# E-cabinet.net
KiCad netlist of a schematic drawn in EAGLE
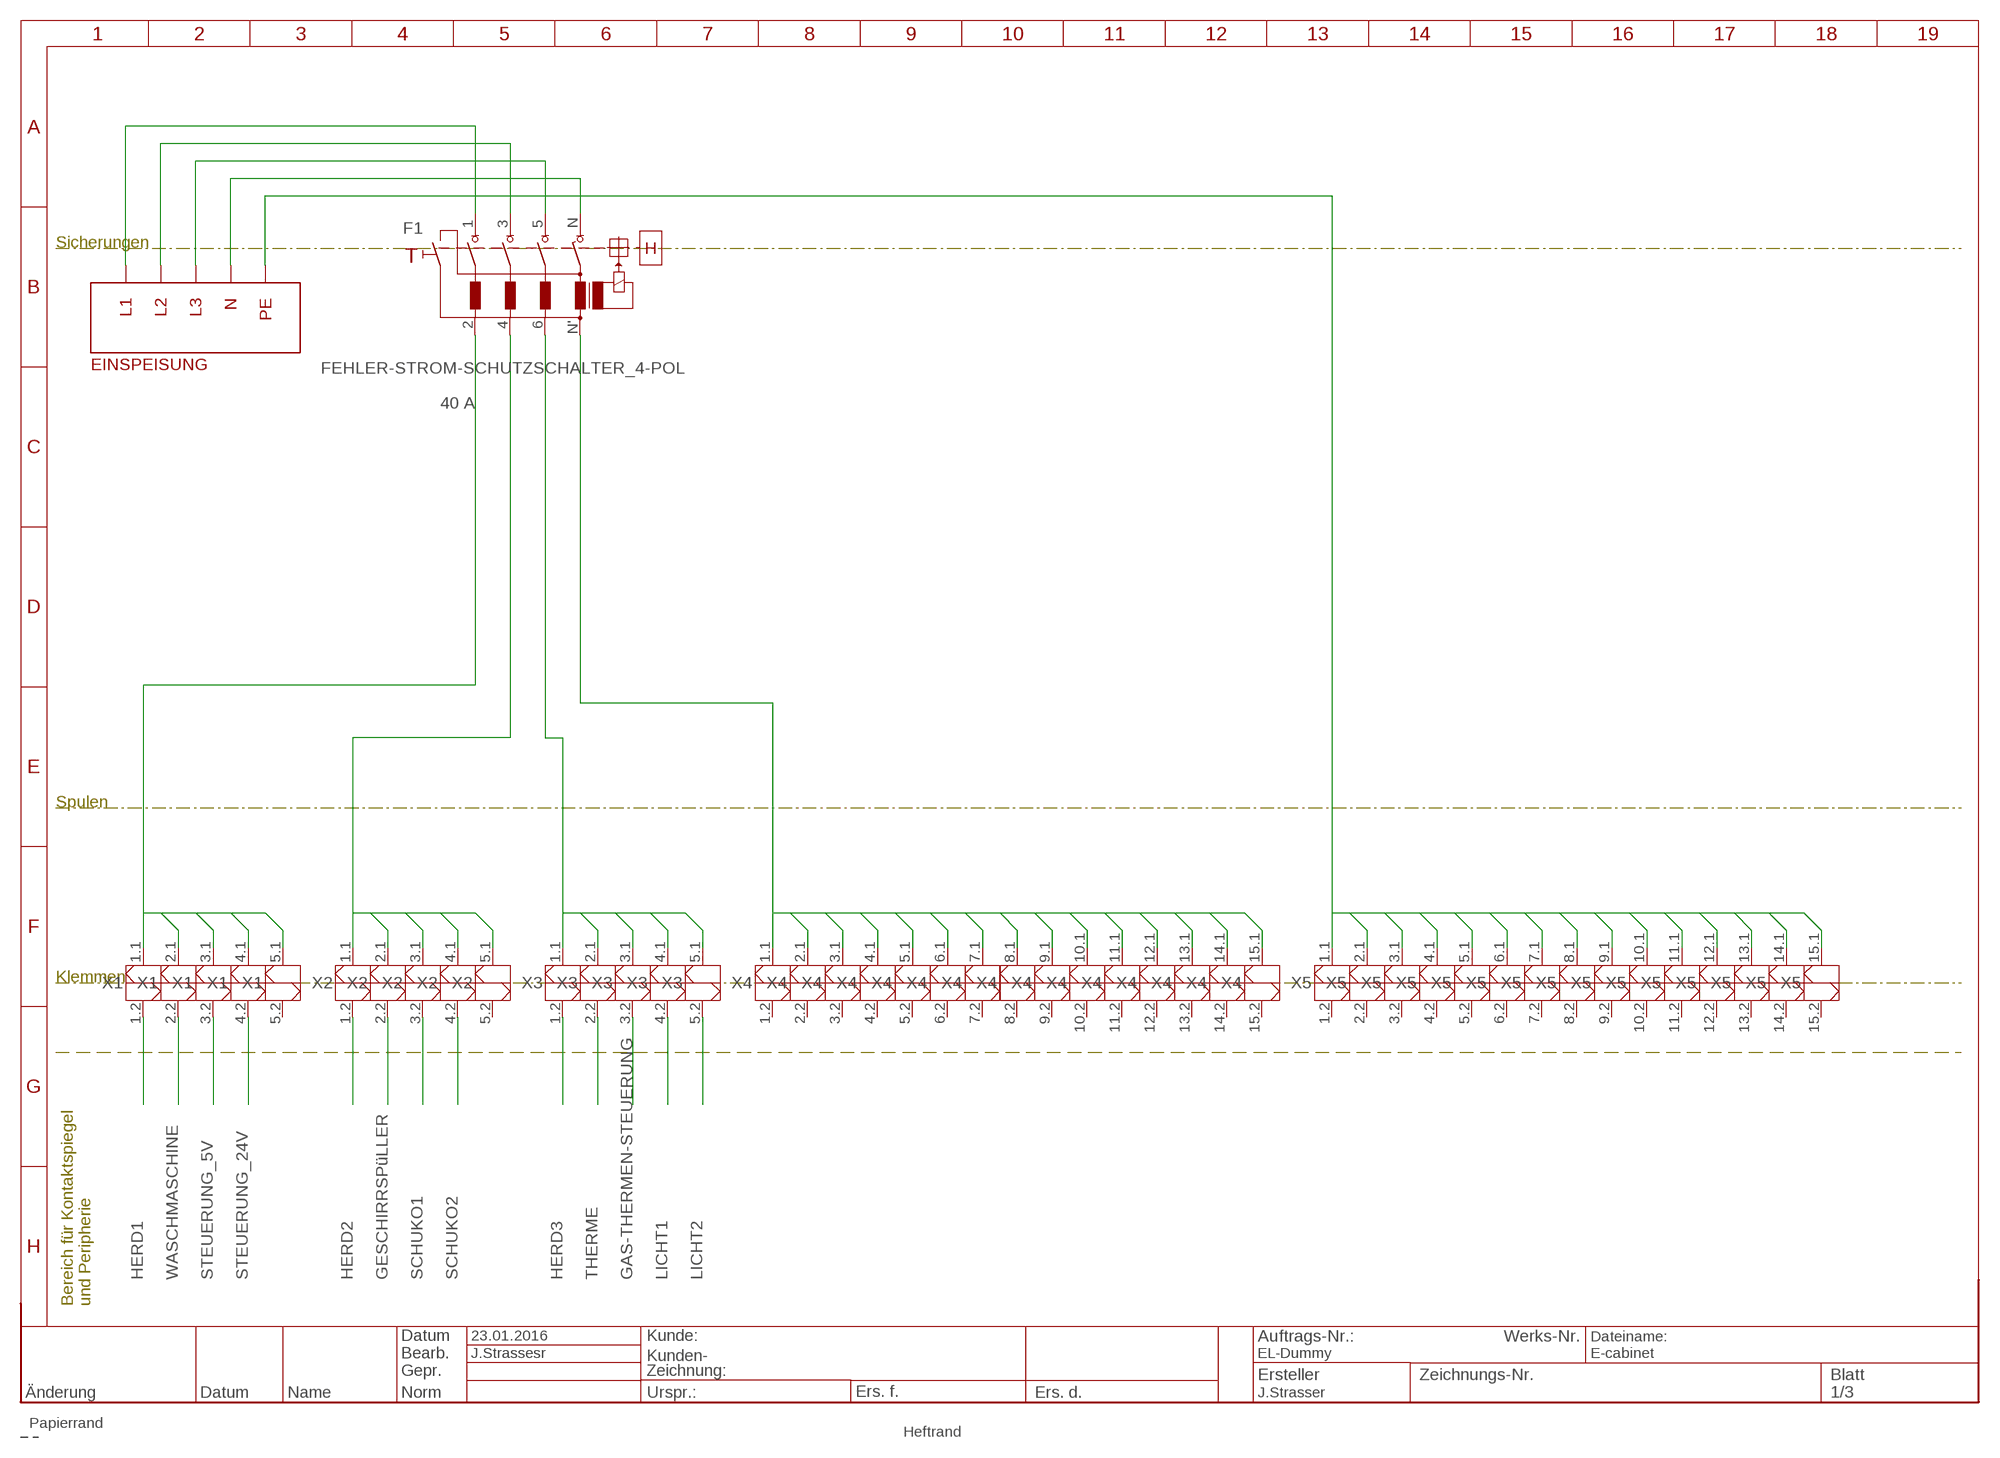
[diagram p0: schematic, sheet 1]
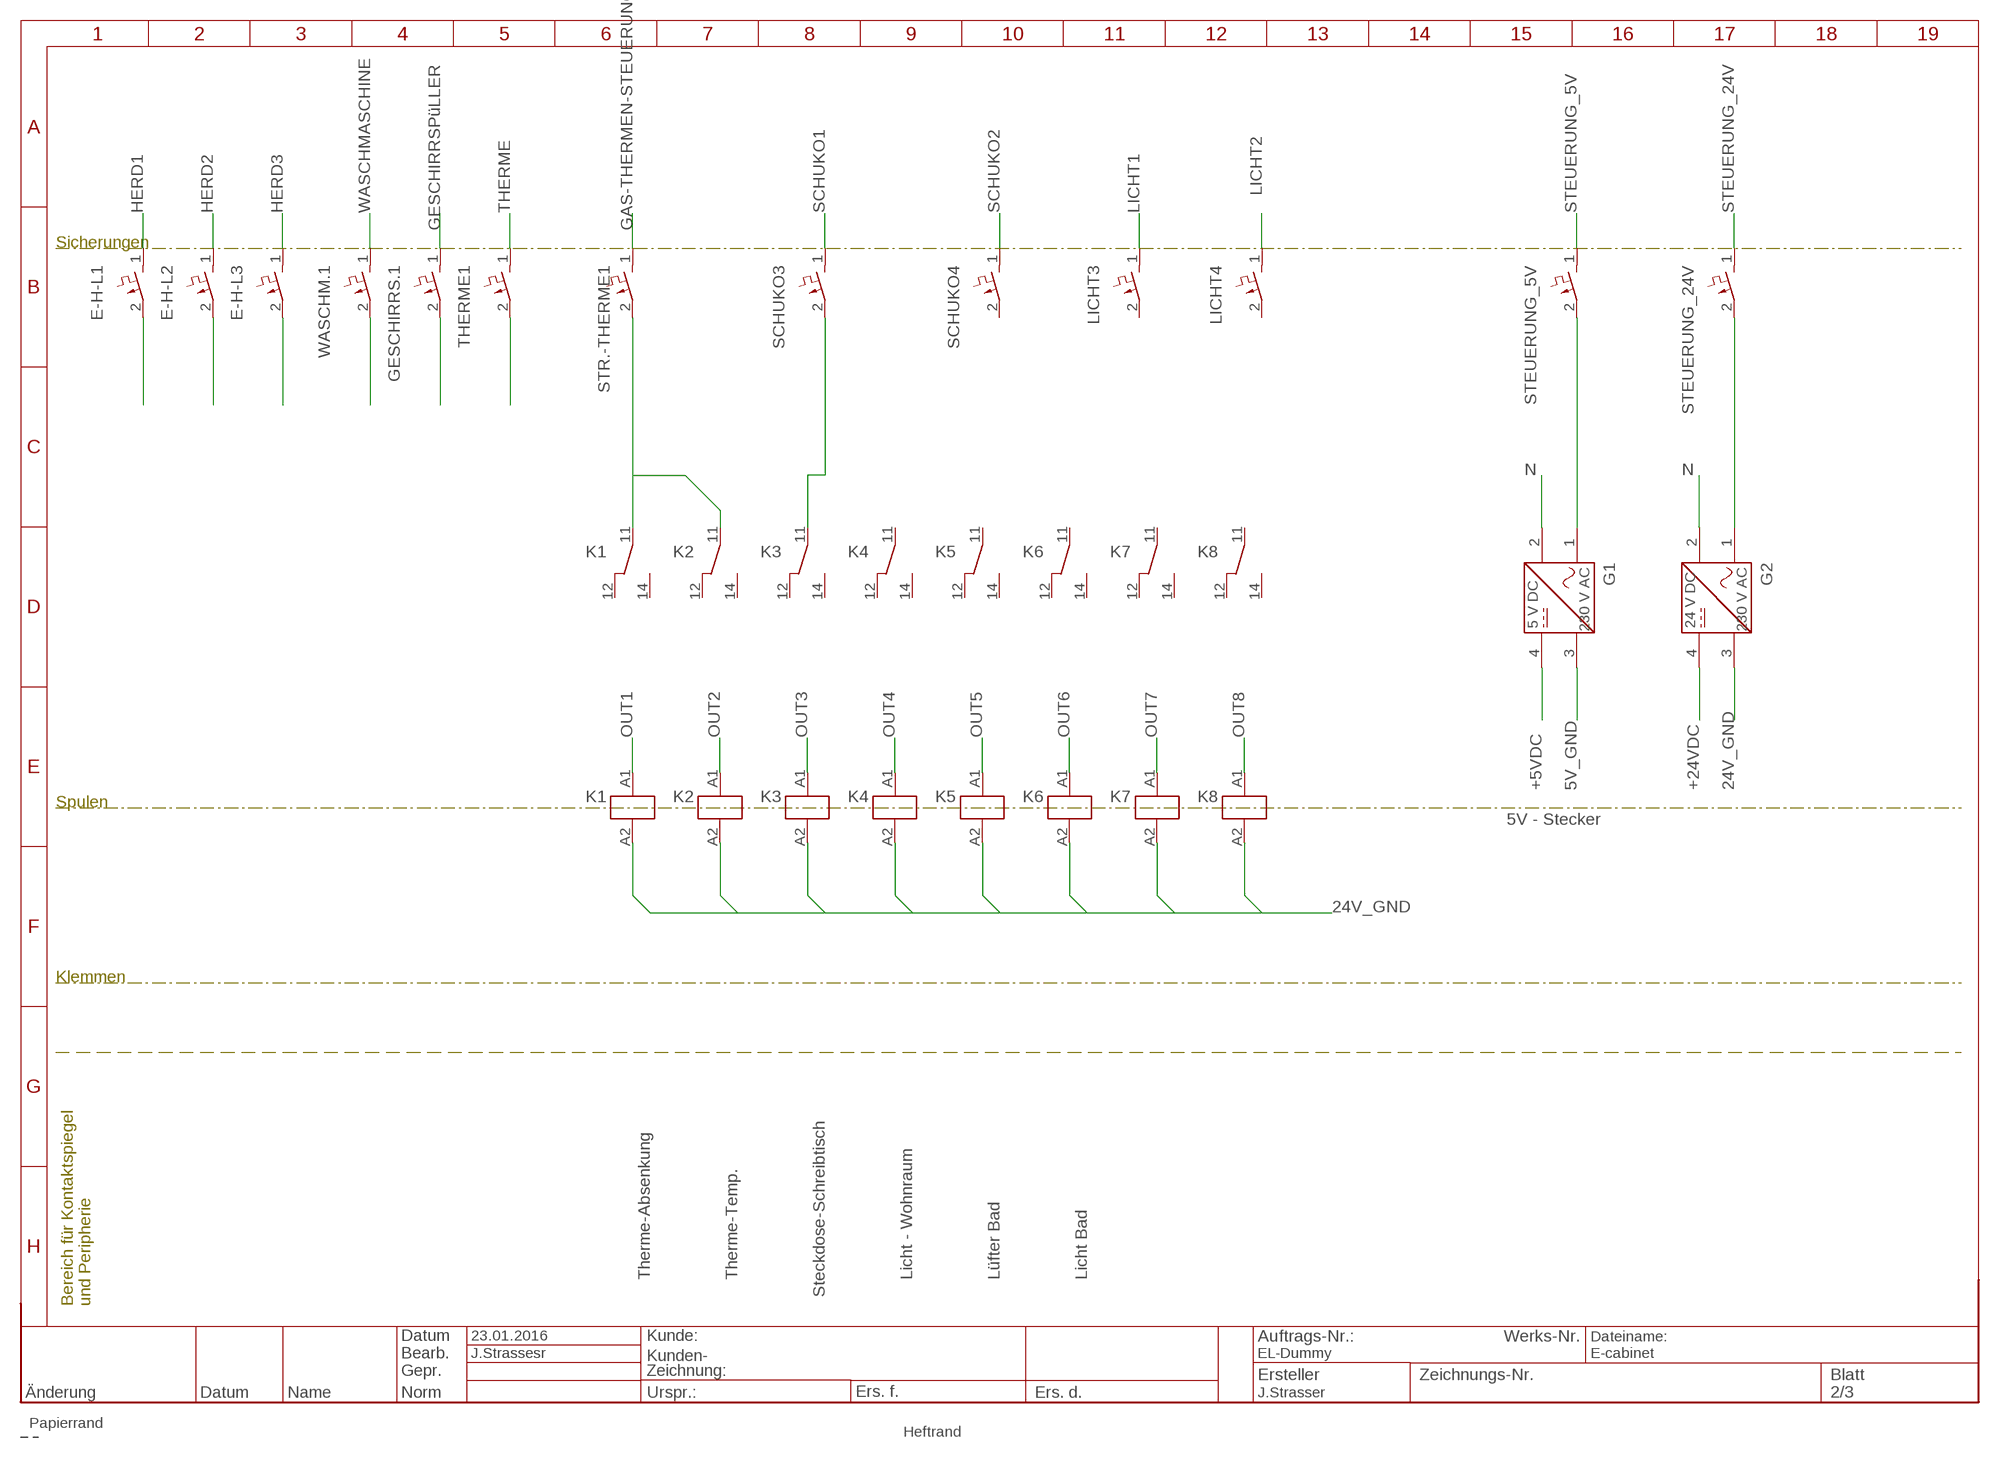
[diagram p1: schematic, sheet 2]
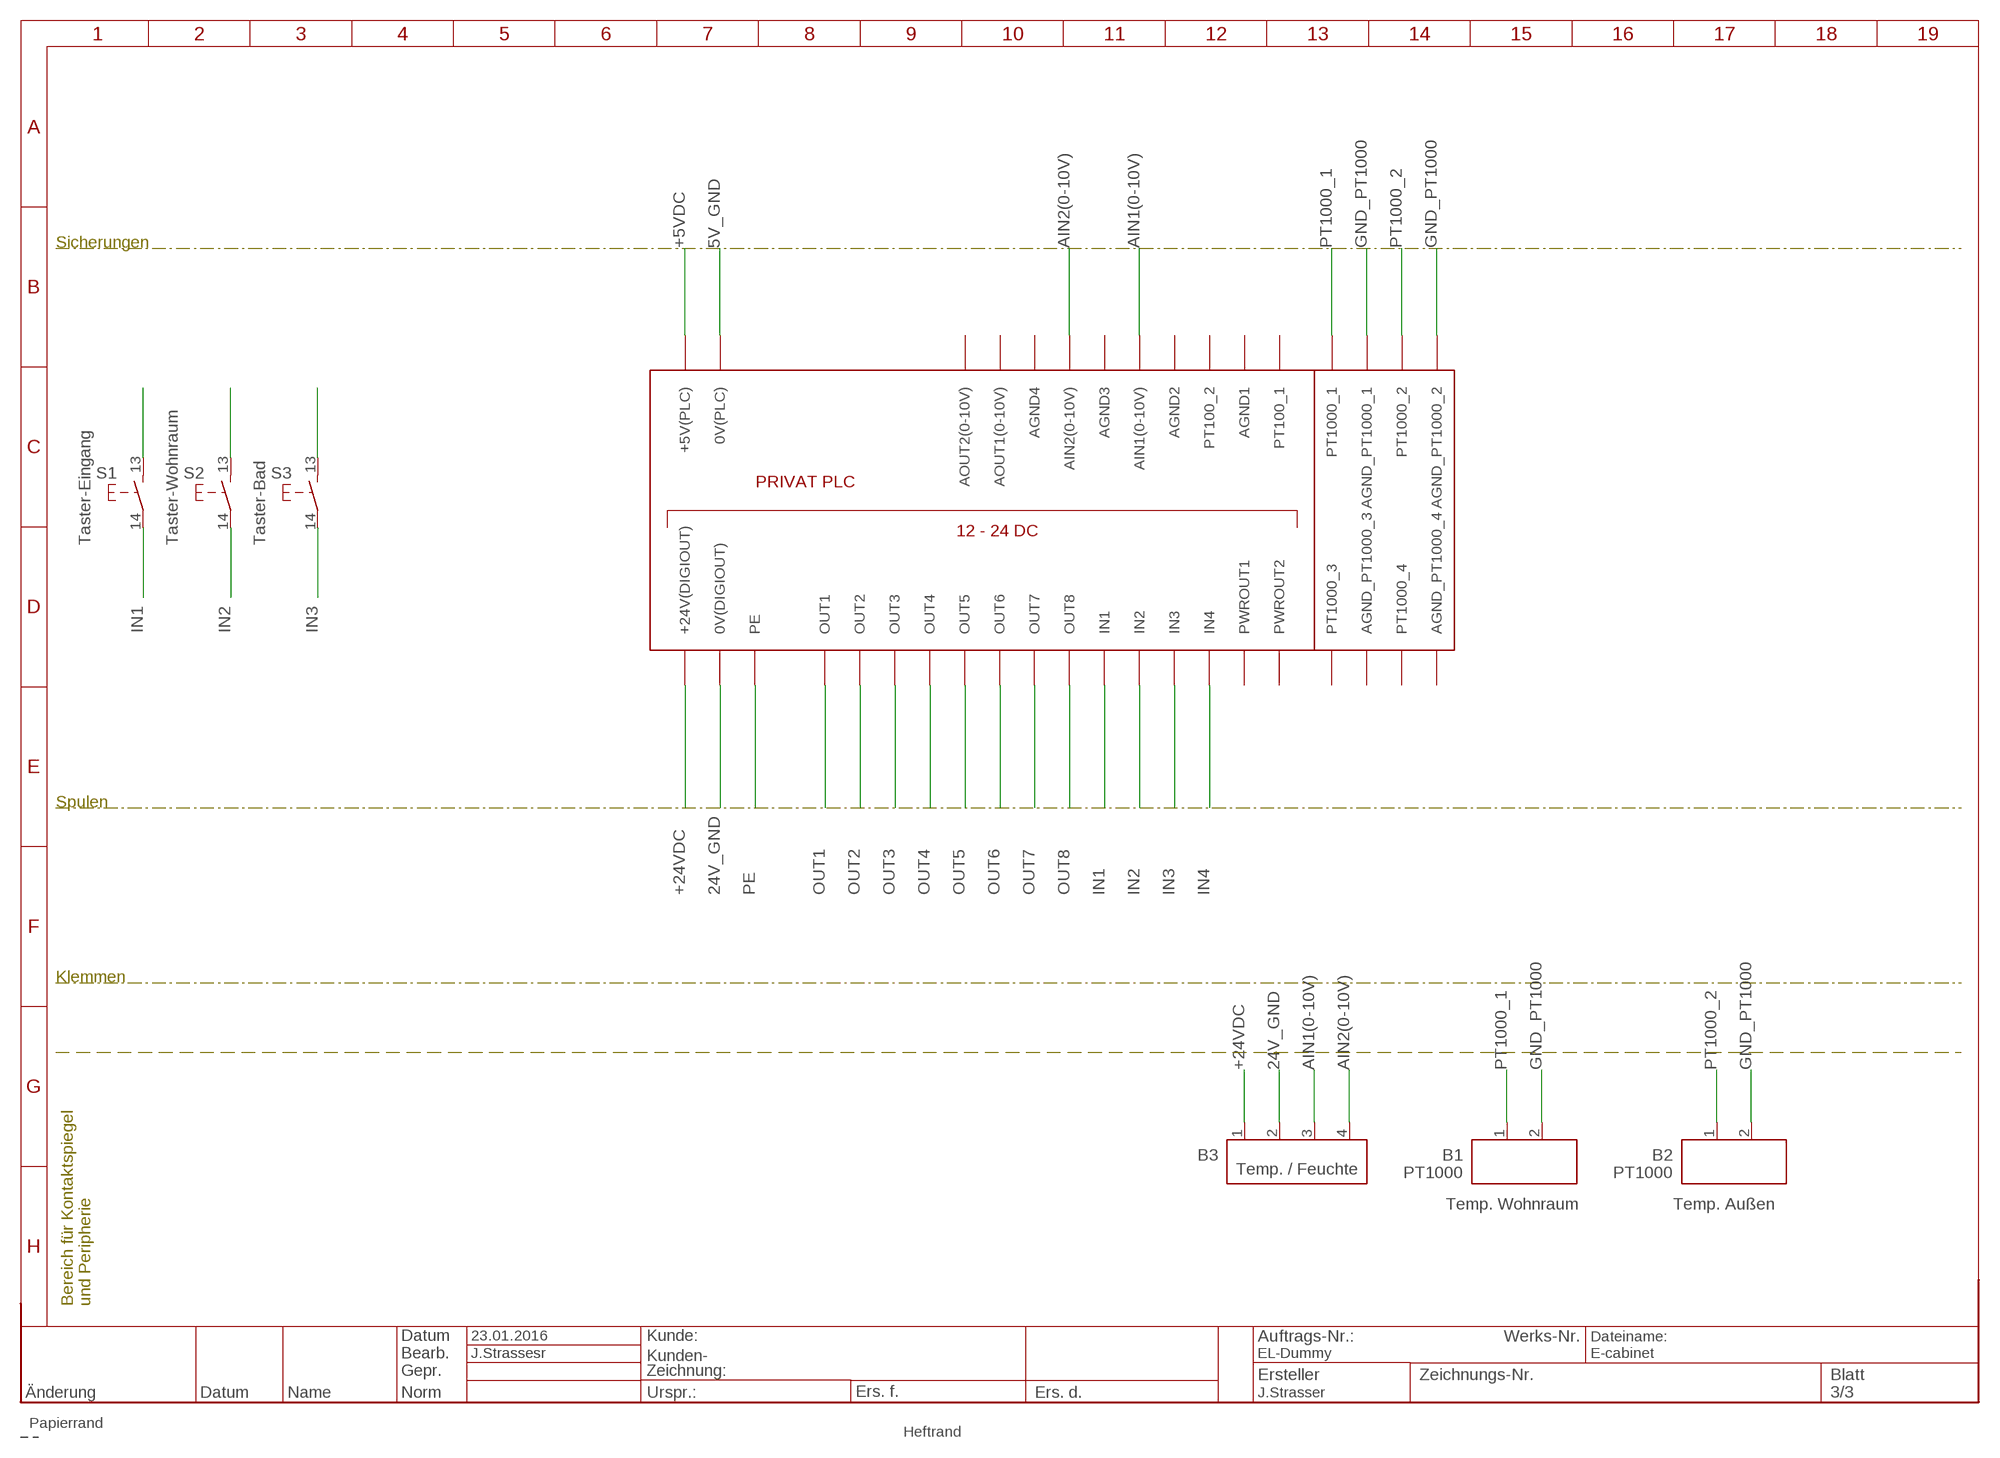
[diagram p2: schematic, sheet 3]

(export (version "E")
  (design (tool "Eeschema 10.0.6"))
  (components
    (comp (ref "E-H-L1")
      (value "LEITUNGSSCHUTZSCHALTER")
      (footprint "eagle-import:LEITUNGSSCHUTZSCHALTER")
      (libsource (lib "eagle-import") (part "LEITUNGSSCHUTZSCHALTER"))
    )
    (comp (ref "E-H-L2")
      (value "LEITUNGSSCHUTZSCHALTER")
      (footprint "eagle-import:LEITUNGSSCHUTZSCHALTER")
      (libsource (lib "eagle-import") (part "LEITUNGSSCHUTZSCHALTER"))
    )
    (comp (ref "E-H-L3")
      (value "LEITUNGSSCHUTZSCHALTER")
      (footprint "eagle-import:LEITUNGSSCHUTZSCHALTER")
      (libsource (lib "eagle-import") (part "LEITUNGSSCHUTZSCHALTER"))
    )
    (comp (ref "G1")
      (value "NETZTEIL_GLEICHSPANNUNG")
      (footprint "eagle-import:NETZTEIL_GLEICHSPANNUNG")
      (fields (field (name "AUSGANGSSPANNUNG") "5 V DC") (field (name "EINGANGSSPANNUNG") "230 V AC"))
      (libsource (lib "eagle-import") (part "NETZTEIL_GLEICHSPANNUNG"))
    )
    (comp (ref "G2")
      (value "NETZTEIL_GLEICHSPANNUNG")
      (footprint "eagle-import:NETZTEIL_GLEICHSPANNUNG")
      (fields (field (name "AUSGANGSSPANNUNG") "24 V DC") (field (name "EINGANGSSPANNUNG") "230 V AC"))
      (libsource (lib "eagle-import") (part "NETZTEIL_GLEICHSPANNUNG"))
    )
    (comp (ref "GESCHIRRS.1")
      (value "LEITUNGSSCHUTZSCHALTER")
      (footprint "eagle-import:LEITUNGSSCHUTZSCHALTER")
      (libsource (lib "eagle-import") (part "LEITUNGSSCHUTZSCHALTER"))
    )
    (comp (ref "K1")
      (value "HILFSSCHUETZ_11-12-14")
      (footprint "eagle-import:HILFSSCHUETZ_11-12-14")
      (libsource (lib "eagle-import") (part "HILFSSCHUETZ_11-12-14"))
    )
    (comp (ref "K2")
      (value "HILFSSCHUETZ_11-12-14")
      (footprint "eagle-import:HILFSSCHUETZ_11-12-14")
      (libsource (lib "eagle-import") (part "HILFSSCHUETZ_11-12-14"))
    )
    (comp (ref "K3")
      (value "HILFSSCHUETZ_11-12-14")
      (footprint "eagle-import:HILFSSCHUETZ_11-12-14")
      (libsource (lib "eagle-import") (part "HILFSSCHUETZ_11-12-14"))
    )
    (comp (ref "K4")
      (value "HILFSSCHUETZ_11-12-14")
      (footprint "eagle-import:HILFSSCHUETZ_11-12-14")
      (libsource (lib "eagle-import") (part "HILFSSCHUETZ_11-12-14"))
    )
    (comp (ref "K5")
      (value "HILFSSCHUETZ_11-12-14")
      (footprint "eagle-import:HILFSSCHUETZ_11-12-14")
      (libsource (lib "eagle-import") (part "HILFSSCHUETZ_11-12-14"))
    )
    (comp (ref "K6")
      (value "HILFSSCHUETZ_11-12-14")
      (footprint "eagle-import:HILFSSCHUETZ_11-12-14")
      (libsource (lib "eagle-import") (part "HILFSSCHUETZ_11-12-14"))
    )
    (comp (ref "K7")
      (value "HILFSSCHUETZ_11-12-14")
      (footprint "eagle-import:HILFSSCHUETZ_11-12-14")
      (libsource (lib "eagle-import") (part "HILFSSCHUETZ_11-12-14"))
    )
    (comp (ref "K8")
      (value "HILFSSCHUETZ_11-12-14")
      (footprint "eagle-import:HILFSSCHUETZ_11-12-14")
      (libsource (lib "eagle-import") (part "HILFSSCHUETZ_11-12-14"))
    )
    (comp (ref "LICHT3")
      (value "LEITUNGSSCHUTZSCHALTER")
      (footprint "eagle-import:LEITUNGSSCHUTZSCHALTER")
      (libsource (lib "eagle-import") (part "LEITUNGSSCHUTZSCHALTER"))
    )
    (comp (ref "LICHT4")
      (value "LEITUNGSSCHUTZSCHALTER")
      (footprint "eagle-import:LEITUNGSSCHUTZSCHALTER")
      (libsource (lib "eagle-import") (part "LEITUNGSSCHUTZSCHALTER"))
    )
    (comp (ref "SCHUKO3")
      (value "LEITUNGSSCHUTZSCHALTER")
      (footprint "eagle-import:LEITUNGSSCHUTZSCHALTER")
      (libsource (lib "eagle-import") (part "LEITUNGSSCHUTZSCHALTER"))
    )
    (comp (ref "SCHUKO4")
      (value "LEITUNGSSCHUTZSCHALTER")
      (footprint "eagle-import:LEITUNGSSCHUTZSCHALTER")
      (libsource (lib "eagle-import") (part "LEITUNGSSCHUTZSCHALTER"))
    )
    (comp (ref "STEUERUNG_5V")
      (value "LEITUNGSSCHUTZSCHALTER")
      (footprint "eagle-import:LEITUNGSSCHUTZSCHALTER")
      (libsource (lib "eagle-import") (part "LEITUNGSSCHUTZSCHALTER"))
    )
    (comp (ref "STEUERUNG_24V")
      (value "LEITUNGSSCHUTZSCHALTER")
      (footprint "eagle-import:LEITUNGSSCHUTZSCHALTER")
      (libsource (lib "eagle-import") (part "LEITUNGSSCHUTZSCHALTER"))
    )
    (comp (ref "STR.-THERME1")
      (value "LEITUNGSSCHUTZSCHALTER")
      (footprint "eagle-import:LEITUNGSSCHUTZSCHALTER")
      (libsource (lib "eagle-import") (part "LEITUNGSSCHUTZSCHALTER"))
    )
    (comp (ref "THERME1")
      (value "LEITUNGSSCHUTZSCHALTER")
      (footprint "eagle-import:LEITUNGSSCHUTZSCHALTER")
      (libsource (lib "eagle-import") (part "LEITUNGSSCHUTZSCHALTER"))
    )
    (comp (ref "WASCHM.1")
      (value "LEITUNGSSCHUTZSCHALTER")
      (footprint "eagle-import:LEITUNGSSCHUTZSCHALTER")
      (libsource (lib "eagle-import") (part "LEITUNGSSCHUTZSCHALTER"))
    )
    (comp (ref "B1")
      (value "MESSFUEHLER_2")
      (footprint "eagle-import:MESSFUEHLER_2")
      (fields (field (name "FUNKTION") "Temp. Wohnraum") (field (name "TYPE") "PT1000"))
      (libsource (lib "eagle-import") (part "MESSFUEHLER_2"))
    )
    (comp (ref "B2")
      (value "MESSFUEHLER_2")
      (footprint "eagle-import:MESSFUEHLER_2")
      (fields (field (name "FUNKTION") "Temp. Außen") (field (name "TYPE") "PT1000"))
      (libsource (lib "eagle-import") (part "MESSFUEHLER_2"))
    )
    (comp (ref "B3")
      (value "MESSFUEHLER_4")
      (footprint "eagle-import:MESSFUEHLER_4")
      (fields (field (name "FUNKTION") "Temp. / Feuchte"))
      (libsource (lib "eagle-import") (part "MESSFUEHLER_4"))
    )
    (comp (ref "S1")
      (value "TASTER_SCHLIESSER")
      (footprint "eagle-import:EINTASTER")
      (libsource (lib "eagle-import") (part "TASTER_SCHLIESSER"))
    )
    (comp (ref "S2")
      (value "TASTER_SCHLIESSER")
      (footprint "eagle-import:EINTASTER")
      (libsource (lib "eagle-import") (part "TASTER_SCHLIESSER"))
    )
    (comp (ref "S3")
      (value "TASTER_SCHLIESSER")
      (footprint "eagle-import:EINTASTER")
      (libsource (lib "eagle-import") (part "TASTER_SCHLIESSER"))
    )
    (comp (ref "U$1")
      (value "PRIVATEPLC")
      (footprint "eagle-import:PRIVATEPLC")
      (libsource (lib "eagle-import") (part "PRIVATEPLC"))
    )
    (comp (ref "F1")
      (value "FEHLER-STROM-SCHUTZSCHALTER_4-POL")
      (footprint "eagle-import:FEHLER-STROM-SCHUTZSCHALTER_4-POL")
      (fields (field (name "FUNKTION") "40 A"))
      (libsource (lib "eagle-import") (part "FEHLER-STROM-SCHUTZSCHALTER_4-POL"))
    )
    (comp (ref "X1")
      (value "KLEMME-2_5-BRUECKE")
      (footprint "eagle-import:KLEMME-2_5-BRUECKE")
      (libsource (lib "eagle-import") (part "KLEMME-2_5-BRUECKE"))
    )
    (comp (ref "X2")
      (value "KLEMME-2_5-BRUECKE")
      (footprint "eagle-import:KLEMME-2_5-BRUECKE")
      (libsource (lib "eagle-import") (part "KLEMME-2_5-BRUECKE"))
    )
    (comp (ref "X3")
      (value "KLEMME-2_5-BRUECKE")
      (footprint "eagle-import:KLEMME-2_5-BRUECKE")
      (libsource (lib "eagle-import") (part "KLEMME-2_5-BRUECKE"))
    )
    (comp (ref "X4")
      (value "KLEMME-2_15-BRUECKE")
      (footprint "eagle-import:KLEMME-2_15-BRUECKE")
      (libsource (lib "eagle-import") (part "KLEMME-2_15-BRUECKE"))
    )
    (comp (ref "X5")
      (value "KLEMME-2_15-BRUECKE")
      (footprint "eagle-import:KLEMME-2_15-BRUECKE")
      (libsource (lib "eagle-import") (part "KLEMME-2_15-BRUECKE"))
    )
  )
  (nets
    (net (code "1") (name "+5VDC") (class "Default")
      (node (ref "G1") (pin "4") (pinfunction "4_4") (pintype "passive"))
      (node (ref "U$1") (pin "P5V") (pinfunction "+5V(PLC)_P5V") (pintype "power_in"))
    )
    (net (code "2") (name "+24VDC") (class "Default")
      (node (ref "B3") (pin "1") (pinfunction "1_1") (pintype "passive"))
      (node (ref "G2") (pin "4") (pinfunction "4_4") (pintype "passive"))
      (node (ref "U$1") (pin "+24V") (pinfunction "+24V(DIGIOUT)_+24V") (pintype "power_in"))
    )
    (net (code "3") (name "5V_GND") (class "Default")
      (node (ref "G1") (pin "3") (pinfunction "3_3") (pintype "passive"))
      (node (ref "U$1") (pin "P0V") (pinfunction "0V(PLC)_P0V") (pintype "power_in"))
    )
    (net (code "4") (name "24V_GND") (class "Default")
      (node (ref "B3") (pin "2") (pinfunction "2_2") (pintype "passive"))
      (node (ref "G2") (pin "3") (pinfunction "3_3") (pintype "passive"))
      (node (ref "K1") (pin "A2") (pinfunction "A2_A2") (pintype "input"))
      (node (ref "K2") (pin "A2") (pinfunction "A2_A2") (pintype "input"))
      (node (ref "K3") (pin "A2") (pinfunction "A2_A2") (pintype "input"))
      (node (ref "K4") (pin "A2") (pinfunction "A2_A2") (pintype "input"))
      (node (ref "K5") (pin "A2") (pinfunction "A2_A2") (pintype "input"))
      (node (ref "K6") (pin "A2") (pinfunction "A2_A2") (pintype "input"))
      (node (ref "K7") (pin "A2") (pinfunction "A2_A2") (pintype "input"))
      (node (ref "K8") (pin "A2") (pinfunction "A2_A2") (pintype "input"))
      (node (ref "U$1") (pin "0V") (pinfunction "0V(DIGIOUT)_0V") (pintype "power_in"))
    )
    (net (code "5") (name "AIN1(0-10V)") (class "Default")
      (node (ref "B3") (pin "3") (pinfunction "3_3") (pintype "passive"))
      (node (ref "U$1") (pin "AIN1") (pinfunction "AIN1(0-10V)_AIN1") (pintype "bidirectional"))
    )
    (net (code "6") (name "AIN2(0-10V)") (class "Default")
      (node (ref "B3") (pin "4") (pinfunction "4_4") (pintype "passive"))
      (node (ref "U$1") (pin "AIN2") (pinfunction "AIN2(0-10V)_AIN2") (pintype "bidirectional"))
    )
    (net (code "7") (name "GAS-THERMEN-STEUERUNG") (class "Default")
      (node (ref "STR.-THERME1") (pin "1") (pinfunction "1_1") (pintype "passive"))
      (node (ref "X3") (pin "3.2") (pinfunction "2_3.2") (pintype "passive"))
    )
    (net (code "8") (name "GESCHIRRSPüLLER") (class "Default")
      (node (ref "GESCHIRRS.1") (pin "1") (pinfunction "1_1") (pintype "passive"))
      (node (ref "X2") (pin "2.2") (pinfunction "2_2.2") (pintype "passive"))
    )
    (net (code "9") (name "GND_PT1000") (class "Default")
      (node (ref "B1") (pin "2") (pinfunction "2_2") (pintype "passive"))
      (node (ref "B2") (pin "2") (pinfunction "2_2") (pintype "passive"))
      (node (ref "U$1") (pin "AGND_PT1000_1") (pinfunction "AGND_PT1000_1_AGND_PT1000_1") (pintype "bidirectional"))
      (node (ref "U$1") (pin "AGND_PT1000_2") (pinfunction "AGND_PT1000_2_AGND_PT1000_2") (pintype "bidirectional"))
    )
    (net (code "10") (name "HERD1") (class "Default")
      (node (ref "E-H-L1") (pin "1") (pinfunction "1_1") (pintype "passive"))
      (node (ref "X1") (pin "1.2") (pinfunction "2_1.2") (pintype "passive"))
    )
    (net (code "11") (name "HERD2") (class "Default")
      (node (ref "E-H-L2") (pin "1") (pinfunction "1_1") (pintype "passive"))
      (node (ref "X2") (pin "1.2") (pinfunction "2_1.2") (pintype "passive"))
    )
    (net (code "12") (name "HERD3") (class "Default")
      (node (ref "E-H-L3") (pin "1") (pinfunction "1_1") (pintype "passive"))
      (node (ref "X3") (pin "1.2") (pinfunction "2_1.2") (pintype "passive"))
    )
    (net (code "13") (name "IN1") (class "Default")
      (node (ref "S1") (pin "14") (pinfunction "14_14") (pintype "passive"))
      (node (ref "U$1") (pin "IN1") (pinfunction "IN1_IN1") (pintype "bidirectional"))
    )
    (net (code "14") (name "IN2") (class "Default")
      (node (ref "S2") (pin "14") (pinfunction "14_14") (pintype "passive"))
      (node (ref "U$1") (pin "IN2") (pinfunction "IN2_IN2") (pintype "bidirectional"))
    )
    (net (code "15") (name "IN3") (class "Default")
      (node (ref "S3") (pin "14") (pinfunction "14_14") (pintype "passive"))
      (node (ref "U$1") (pin "IN3") (pinfunction "IN3_IN3") (pintype "bidirectional"))
    )
    (net (code "16") (name "IN4") (class "Default")
      (node (ref "U$1") (pin "IN4") (pinfunction "IN4_IN4") (pintype "bidirectional"))
    )
    (net (code "17") (name "LICHT1") (class "Default")
      (node (ref "LICHT3") (pin "1") (pinfunction "1_1") (pintype "passive"))
      (node (ref "X3") (pin "4.2") (pinfunction "2_4.2") (pintype "passive"))
    )
    (net (code "18") (name "LICHT2") (class "Default")
      (node (ref "LICHT4") (pin "1") (pinfunction "1_1") (pintype "passive"))
      (node (ref "X3") (pin "5.2") (pinfunction "2_5.2") (pintype "passive"))
    )
    (net (code "19") (name "N") (class "Default")
      (node (ref "F1") (pin "N'") (pinfunction "N'_N'") (pintype "passive"))
      (node (ref "G1") (pin "2") (pinfunction "2_2") (pintype "passive"))
      (node (ref "G2") (pin "2") (pinfunction "2_2") (pintype "passive"))
      (node (ref "X4") (pin "1.1") (pinfunction "1_1.1") (pintype "passive"))
      (node (ref "X4") (pin "10.1") (pinfunction "1_10.1") (pintype "passive"))
      (node (ref "X4") (pin "11.1") (pinfunction "1_11.1") (pintype "passive"))
      (node (ref "X4") (pin "12.1") (pinfunction "1_12.1") (pintype "passive"))
      (node (ref "X4") (pin "13.1") (pinfunction "1_13.1") (pintype "passive"))
      (node (ref "X4") (pin "14.1") (pinfunction "1_14.1") (pintype "passive"))
      (node (ref "X4") (pin "15.1") (pinfunction "1_15.1") (pintype "passive"))
      (node (ref "X4") (pin "2.1") (pinfunction "1_2.1") (pintype "passive"))
      (node (ref "X4") (pin "3.1") (pinfunction "1_3.1") (pintype "passive"))
      (node (ref "X4") (pin "4.1") (pinfunction "1_4.1") (pintype "passive"))
      (node (ref "X4") (pin "5.1") (pinfunction "1_5.1") (pintype "passive"))
      (node (ref "X4") (pin "6.1") (pinfunction "1_6.1") (pintype "passive"))
      (node (ref "X4") (pin "7.1") (pinfunction "1_7.1") (pintype "passive"))
      (node (ref "X4") (pin "8.1") (pinfunction "1_8.1") (pintype "passive"))
      (node (ref "X4") (pin "9.1") (pinfunction "1_9.1") (pintype "passive"))
    )
    (net (code "20") (name "Net-(F1-Pad1)") (class "Default")
      (node (ref "F1") (pin "1") (pinfunction "1_1") (pintype "passive"))
    )
    (net (code "21") (name "Net-(F1-Pad3)") (class "Default")
      (node (ref "F1") (pin "3") (pinfunction "3_3") (pintype "passive"))
    )
    (net (code "22") (name "Net-(F1-Pad5)") (class "Default")
      (node (ref "F1") (pin "5") (pinfunction "5_5") (pintype "passive"))
    )
    (net (code "23") (name "Net-(F1-PadN)") (class "Default")
      (node (ref "F1") (pin "N") (pinfunction "N_N") (pintype "passive"))
    )
    (net (code "24") (name "Net-(G1-Pad1)") (class "Default")
      (node (ref "G1") (pin "1") (pinfunction "1_1") (pintype "passive"))
      (node (ref "STEUERUNG_5V") (pin "2") (pinfunction "2_2") (pintype "passive"))
    )
    (net (code "25") (name "Net-(G2-Pad1)") (class "Default")
      (node (ref "G2") (pin "1") (pinfunction "1_1") (pintype "passive"))
      (node (ref "STEUERUNG_24V") (pin "2") (pinfunction "2_2") (pintype "passive"))
    )
    (net (code "26") (name "Net-(K1B-1)") (class "Default")
      (node (ref "K1") (pin "11") (pinfunction "1_11") (pintype "passive"))
      (node (ref "K2") (pin "11") (pinfunction "1_11") (pintype "passive"))
      (node (ref "STR.-THERME1") (pin "2") (pinfunction "2_2") (pintype "passive"))
    )
    (net (code "27") (name "Net-(K3B-1)") (class "Default")
      (node (ref "K3") (pin "11") (pinfunction "1_11") (pintype "passive"))
      (node (ref "SCHUKO3") (pin "2") (pinfunction "2_2") (pintype "passive"))
    )
    (net (code "28") (name "Net-(X1A-1)") (class "Default")
      (node (ref "F1") (pin "2") (pinfunction "2_2") (pintype "passive"))
      (node (ref "X1") (pin "1.1") (pinfunction "1_1.1") (pintype "passive"))
      (node (ref "X1") (pin "2.1") (pinfunction "1_2.1") (pintype "passive"))
      (node (ref "X1") (pin "3.1") (pinfunction "1_3.1") (pintype "passive"))
      (node (ref "X1") (pin "4.1") (pinfunction "1_4.1") (pintype "passive"))
      (node (ref "X1") (pin "5.1") (pinfunction "1_5.1") (pintype "passive"))
    )
    (net (code "29") (name "Net-(X2A-1)") (class "Default")
      (node (ref "F1") (pin "4") (pinfunction "4_4") (pintype "passive"))
      (node (ref "X2") (pin "1.1") (pinfunction "1_1.1") (pintype "passive"))
      (node (ref "X2") (pin "2.1") (pinfunction "1_2.1") (pintype "passive"))
      (node (ref "X2") (pin "3.1") (pinfunction "1_3.1") (pintype "passive"))
      (node (ref "X2") (pin "4.1") (pinfunction "1_4.1") (pintype "passive"))
      (node (ref "X2") (pin "5.1") (pinfunction "1_5.1") (pintype "passive"))
    )
    (net (code "30") (name "Net-(X3A-1)") (class "Default")
      (node (ref "F1") (pin "6") (pinfunction "6_6") (pintype "passive"))
      (node (ref "X3") (pin "1.1") (pinfunction "1_1.1") (pintype "passive"))
      (node (ref "X3") (pin "2.1") (pinfunction "1_2.1") (pintype "passive"))
      (node (ref "X3") (pin "3.1") (pinfunction "1_3.1") (pintype "passive"))
      (node (ref "X3") (pin "4.1") (pinfunction "1_4.1") (pintype "passive"))
      (node (ref "X3") (pin "5.1") (pinfunction "1_5.1") (pintype "passive"))
    )
    (net (code "31") (name "Net-(X5A-1)") (class "Default")
      (node (ref "X5") (pin "1.1") (pinfunction "1_1.1") (pintype "passive"))
      (node (ref "X5") (pin "10.1") (pinfunction "1_10.1") (pintype "passive"))
      (node (ref "X5") (pin "11.1") (pinfunction "1_11.1") (pintype "passive"))
      (node (ref "X5") (pin "12.1") (pinfunction "1_12.1") (pintype "passive"))
      (node (ref "X5") (pin "13.1") (pinfunction "1_13.1") (pintype "passive"))
      (node (ref "X5") (pin "14.1") (pinfunction "1_14.1") (pintype "passive"))
      (node (ref "X5") (pin "15.1") (pinfunction "1_15.1") (pintype "passive"))
      (node (ref "X5") (pin "2.1") (pinfunction "1_2.1") (pintype "passive"))
      (node (ref "X5") (pin "3.1") (pinfunction "1_3.1") (pintype "passive"))
      (node (ref "X5") (pin "4.1") (pinfunction "1_4.1") (pintype "passive"))
      (node (ref "X5") (pin "5.1") (pinfunction "1_5.1") (pintype "passive"))
      (node (ref "X5") (pin "6.1") (pinfunction "1_6.1") (pintype "passive"))
      (node (ref "X5") (pin "7.1") (pinfunction "1_7.1") (pintype "passive"))
      (node (ref "X5") (pin "8.1") (pinfunction "1_8.1") (pintype "passive"))
      (node (ref "X5") (pin "9.1") (pinfunction "1_9.1") (pintype "passive"))
    )
    (net (code "32") (name "OUT1") (class "Default")
      (node (ref "K1") (pin "A1") (pinfunction "A1_A1") (pintype "input"))
      (node (ref "U$1") (pin "OUT1") (pinfunction "OUT1_OUT1") (pintype "bidirectional"))
    )
    (net (code "33") (name "OUT2") (class "Default")
      (node (ref "K2") (pin "A1") (pinfunction "A1_A1") (pintype "input"))
      (node (ref "U$1") (pin "OUT2") (pinfunction "OUT2_OUT2") (pintype "bidirectional"))
    )
    (net (code "34") (name "OUT3") (class "Default")
      (node (ref "K3") (pin "A1") (pinfunction "A1_A1") (pintype "input"))
      (node (ref "U$1") (pin "OUT3") (pinfunction "OUT3_OUT3") (pintype "bidirectional"))
    )
    (net (code "35") (name "OUT4") (class "Default")
      (node (ref "K4") (pin "A1") (pinfunction "A1_A1") (pintype "input"))
      (node (ref "U$1") (pin "OUT4") (pinfunction "OUT4_OUT4") (pintype "bidirectional"))
    )
    (net (code "36") (name "OUT5") (class "Default")
      (node (ref "K5") (pin "A1") (pinfunction "A1_A1") (pintype "input"))
      (node (ref "U$1") (pin "OUT5") (pinfunction "OUT5_OUT5") (pintype "bidirectional"))
    )
    (net (code "37") (name "OUT6") (class "Default")
      (node (ref "K6") (pin "A1") (pinfunction "A1_A1") (pintype "input"))
      (node (ref "U$1") (pin "OUT6") (pinfunction "OUT6_OUT6") (pintype "bidirectional"))
    )
    (net (code "38") (name "OUT7") (class "Default")
      (node (ref "K7") (pin "A1") (pinfunction "A1_A1") (pintype "input"))
      (node (ref "U$1") (pin "OUT7") (pinfunction "OUT7_OUT7") (pintype "bidirectional"))
    )
    (net (code "39") (name "OUT8") (class "Default")
      (node (ref "K8") (pin "A1") (pinfunction "A1_A1") (pintype "input"))
      (node (ref "U$1") (pin "OUT8") (pinfunction "OUT8_OUT8") (pintype "bidirectional"))
    )
    (net (code "40") (name "PE") (class "Default")
      (node (ref "U$1") (pin "PE") (pinfunction "PE_PE") (pintype "power_in"))
    )
    (net (code "41") (name "PT1000_1") (class "Default")
      (node (ref "B1") (pin "1") (pinfunction "1_1") (pintype "passive"))
      (node (ref "U$1") (pin "PT1000_1") (pinfunction "PT1000_1_PT1000_1") (pintype "bidirectional"))
    )
    (net (code "42") (name "PT1000_2") (class "Default")
      (node (ref "B2") (pin "1") (pinfunction "1_1") (pintype "passive"))
      (node (ref "U$1") (pin "PT1000_2") (pinfunction "PT1000_2_PT1000_2") (pintype "bidirectional"))
    )
    (net (code "43") (name "PWROUT1") (class "Default")
      (node (ref "U$1") (pin "PWROUT1") (pinfunction "PWROUT1_PWROUT1") (pintype "power_in"))
    )
    (net (code "44") (name "PWROUT2") (class "Default")
      (node (ref "U$1") (pin "PWROUT2") (pinfunction "PWROUT2_PWROUT2") (pintype "power_in"))
    )
    (net (code "45") (name "SCHUKO1") (class "Default")
      (node (ref "SCHUKO3") (pin "1") (pinfunction "1_1") (pintype "passive"))
      (node (ref "X2") (pin "3.2") (pinfunction "2_3.2") (pintype "passive"))
    )
    (net (code "46") (name "SCHUKO2") (class "Default")
      (node (ref "SCHUKO4") (pin "1") (pinfunction "1_1") (pintype "passive"))
      (node (ref "X2") (pin "4.2") (pinfunction "2_4.2") (pintype "passive"))
    )
    (net (code "47") (name "STEUERUNG_5V") (class "Default")
      (node (ref "STEUERUNG_5V") (pin "1") (pinfunction "1_1") (pintype "passive"))
      (node (ref "X1") (pin "3.2") (pinfunction "2_3.2") (pintype "passive"))
    )
    (net (code "48") (name "STEUERUNG_24V") (class "Default")
      (node (ref "STEUERUNG_24V") (pin "1") (pinfunction "1_1") (pintype "passive"))
      (node (ref "X1") (pin "4.2") (pinfunction "2_4.2") (pintype "passive"))
    )
    (net (code "49") (name "THERME") (class "Default")
      (node (ref "THERME1") (pin "1") (pinfunction "1_1") (pintype "passive"))
      (node (ref "X3") (pin "2.2") (pinfunction "2_2.2") (pintype "passive"))
    )
    (net (code "50") (name "WASCHMASCHINE") (class "Default")
      (node (ref "WASCHM.1") (pin "1") (pinfunction "1_1") (pintype "passive"))
      (node (ref "X1") (pin "2.2") (pinfunction "2_2.2") (pintype "passive"))
    )
    (net (code "51") (name "unconnected-(E-H-L1-Pad2)") (class "Default")
      (node (ref "E-H-L1") (pin "2") (pinfunction "2_2") (pintype "passive"))
    )
    (net (code "52") (name "unconnected-(E-H-L2-Pad2)") (class "Default")
      (node (ref "E-H-L2") (pin "2") (pinfunction "2_2") (pintype "passive"))
    )
    (net (code "53") (name "unconnected-(E-H-L3-Pad2)") (class "Default")
      (node (ref "E-H-L3") (pin "2") (pinfunction "2_2") (pintype "passive"))
    )
    (net (code "54") (name "unconnected-(GESCHIRRS.1-Pad2)") (class "Default")
      (node (ref "GESCHIRRS.1") (pin "2") (pinfunction "2_2") (pintype "passive"))
    )
    (net (code "55") (name "unconnected-(K1B-2-Pad12)") (class "Default")
      (node (ref "K1") (pin "12") (pinfunction "2_12") (pintype "passive"))
    )
    (net (code "56") (name "unconnected-(K1B-4-Pad14)") (class "Default")
      (node (ref "K1") (pin "14") (pinfunction "4_14") (pintype "passive"))
    )
    (net (code "57") (name "unconnected-(K2B-2-Pad12)") (class "Default")
      (node (ref "K2") (pin "12") (pinfunction "2_12") (pintype "passive"))
    )
    (net (code "58") (name "unconnected-(K2B-4-Pad14)") (class "Default")
      (node (ref "K2") (pin "14") (pinfunction "4_14") (pintype "passive"))
    )
    (net (code "59") (name "unconnected-(K3B-2-Pad12)") (class "Default")
      (node (ref "K3") (pin "12") (pinfunction "2_12") (pintype "passive"))
    )
    (net (code "60") (name "unconnected-(K3B-4-Pad14)") (class "Default")
      (node (ref "K3") (pin "14") (pinfunction "4_14") (pintype "passive"))
    )
    (net (code "61") (name "unconnected-(K4B-1-Pad11)") (class "Default")
      (node (ref "K4") (pin "11") (pinfunction "1_11") (pintype "passive"))
    )
    (net (code "62") (name "unconnected-(K4B-2-Pad12)") (class "Default")
      (node (ref "K4") (pin "12") (pinfunction "2_12") (pintype "passive"))
    )
    (net (code "63") (name "unconnected-(K4B-4-Pad14)") (class "Default")
      (node (ref "K4") (pin "14") (pinfunction "4_14") (pintype "passive"))
    )
    (net (code "64") (name "unconnected-(K5B-1-Pad11)") (class "Default")
      (node (ref "K5") (pin "11") (pinfunction "1_11") (pintype "passive"))
    )
    (net (code "65") (name "unconnected-(K5B-2-Pad12)") (class "Default")
      (node (ref "K5") (pin "12") (pinfunction "2_12") (pintype "passive"))
    )
    (net (code "66") (name "unconnected-(K5B-4-Pad14)") (class "Default")
      (node (ref "K5") (pin "14") (pinfunction "4_14") (pintype "passive"))
    )
    (net (code "67") (name "unconnected-(K6B-1-Pad11)") (class "Default")
      (node (ref "K6") (pin "11") (pinfunction "1_11") (pintype "passive"))
    )
    (net (code "68") (name "unconnected-(K6B-2-Pad12)") (class "Default")
      (node (ref "K6") (pin "12") (pinfunction "2_12") (pintype "passive"))
    )
    (net (code "69") (name "unconnected-(K6B-4-Pad14)") (class "Default")
      (node (ref "K6") (pin "14") (pinfunction "4_14") (pintype "passive"))
    )
    (net (code "70") (name "unconnected-(K7B-1-Pad11)") (class "Default")
      (node (ref "K7") (pin "11") (pinfunction "1_11") (pintype "passive"))
    )
    (net (code "71") (name "unconnected-(K7B-2-Pad12)") (class "Default")
      (node (ref "K7") (pin "12") (pinfunction "2_12") (pintype "passive"))
    )
    (net (code "72") (name "unconnected-(K7B-4-Pad14)") (class "Default")
      (node (ref "K7") (pin "14") (pinfunction "4_14") (pintype "passive"))
    )
    (net (code "73") (name "unconnected-(K8B-1-Pad11)") (class "Default")
      (node (ref "K8") (pin "11") (pinfunction "1_11") (pintype "passive"))
    )
    (net (code "74") (name "unconnected-(K8B-2-Pad12)") (class "Default")
      (node (ref "K8") (pin "12") (pinfunction "2_12") (pintype "passive"))
    )
    (net (code "75") (name "unconnected-(K8B-4-Pad14)") (class "Default")
      (node (ref "K8") (pin "14") (pinfunction "4_14") (pintype "passive"))
    )
    (net (code "76") (name "unconnected-(LICHT3-Pad2)") (class "Default")
      (node (ref "LICHT3") (pin "2") (pinfunction "2_2") (pintype "passive"))
    )
    (net (code "77") (name "unconnected-(LICHT4-Pad2)") (class "Default")
      (node (ref "LICHT4") (pin "2") (pinfunction "2_2") (pintype "passive"))
    )
    (net (code "78") (name "unconnected-(S1-Pad13)") (class "Default")
      (node (ref "S1") (pin "13") (pinfunction "13_13") (pintype "passive"))
    )
    (net (code "79") (name "unconnected-(S2-Pad13)") (class "Default")
      (node (ref "S2") (pin "13") (pinfunction "13_13") (pintype "passive"))
    )
    (net (code "80") (name "unconnected-(S3-Pad13)") (class "Default")
      (node (ref "S3") (pin "13") (pinfunction "13_13") (pintype "passive"))
    )
    (net (code "81") (name "unconnected-(SCHUKO4-Pad2)") (class "Default")
      (node (ref "SCHUKO4") (pin "2") (pinfunction "2_2") (pintype "passive"))
    )
    (net (code "82") (name "unconnected-(THERME1-Pad2)") (class "Default")
      (node (ref "THERME1") (pin "2") (pinfunction "2_2") (pintype "passive"))
    )
    (net (code "83") (name "unconnected-(U$1-AOUT1(0-10V)-PadAOUT1)") (class "Default")
      (node (ref "U$1") (pin "AOUT1") (pinfunction "AOUT1(0-10V)_AOUT1") (pintype "bidirectional"))
    )
    (net (code "84") (name "unconnected-(U$1-AOUT2(0-10V)-PadAOUT2)") (class "Default")
      (node (ref "U$1") (pin "AOUT2") (pinfunction "AOUT2(0-10V)_AOUT2") (pintype "bidirectional"))
    )
    (net (code "85") (name "unconnected-(U$1-PadAGND1)") (class "Default")
      (node (ref "U$1") (pin "AGND1") (pinfunction "AGND1_AGND1") (pintype "bidirectional"))
    )
    (net (code "86") (name "unconnected-(U$1-PadAGND2)") (class "Default")
      (node (ref "U$1") (pin "AGND2") (pinfunction "AGND2_AGND2") (pintype "bidirectional"))
    )
    (net (code "87") (name "unconnected-(U$1-PadAGND3)") (class "Default")
      (node (ref "U$1") (pin "AGND3") (pinfunction "AGND3_AGND3") (pintype "bidirectional"))
    )
    (net (code "88") (name "unconnected-(U$1-PadAGND4)") (class "Default")
      (node (ref "U$1") (pin "AGND4") (pinfunction "AGND4_AGND4") (pintype "bidirectional"))
    )
    (net (code "89") (name "unconnected-(U$1-PadAGND_PT1000_3)") (class "Default")
      (node (ref "U$1") (pin "AGND_PT1000_3") (pinfunction "AGND_PT1000_3_AGND_PT1000_3") (pintype "bidirectional"))
    )
    (net (code "90") (name "unconnected-(U$1-PadAGND_PT1000_4)") (class "Default")
      (node (ref "U$1") (pin "AGND_PT1000_4") (pinfunction "AGND_PT1000_4_AGND_PT1000_4") (pintype "bidirectional"))
    )
    (net (code "91") (name "unconnected-(U$1-PadPT100_1)") (class "Default")
      (node (ref "U$1") (pin "PT100_1") (pinfunction "PT100_1_PT100_1") (pintype "bidirectional"))
    )
    (net (code "92") (name "unconnected-(U$1-PadPT100_2)") (class "Default")
      (node (ref "U$1") (pin "PT100_2") (pinfunction "PT100_2_PT100_2") (pintype "bidirectional"))
    )
    (net (code "93") (name "unconnected-(U$1-PadPT1000_3)") (class "Default")
      (node (ref "U$1") (pin "PT1000_3") (pinfunction "PT1000_3_PT1000_3") (pintype "bidirectional"))
    )
    (net (code "94") (name "unconnected-(U$1-PadPT1000_4)") (class "Default")
      (node (ref "U$1") (pin "PT1000_4") (pinfunction "PT1000_4_PT1000_4") (pintype "bidirectional"))
    )
    (net (code "95") (name "unconnected-(WASCHM.1-Pad2)") (class "Default")
      (node (ref "WASCHM.1") (pin "2") (pinfunction "2_2") (pintype "passive"))
    )
    (net (code "96") (name "unconnected-(X1E-2-Pad5.2)") (class "Default")
      (node (ref "X1") (pin "5.2") (pinfunction "2_5.2") (pintype "passive"))
    )
    (net (code "97") (name "unconnected-(X2E-2-Pad5.2)") (class "Default")
      (node (ref "X2") (pin "5.2") (pinfunction "2_5.2") (pintype "passive"))
    )
    (net (code "98") (name "unconnected-(X4A-2-Pad1.2)") (class "Default")
      (node (ref "X4") (pin "1.2") (pinfunction "2_1.2") (pintype "passive"))
    )
    (net (code "99") (name "unconnected-(X4B-2-Pad10.2)") (class "Default")
      (node (ref "X4") (pin "10.2") (pinfunction "2_10.2") (pintype "passive"))
    )
    (net (code "100") (name "unconnected-(X4C-2-Pad11.2)") (class "Default")
      (node (ref "X4") (pin "11.2") (pinfunction "2_11.2") (pintype "passive"))
    )
    (net (code "101") (name "unconnected-(X4D-2-Pad12.2)") (class "Default")
      (node (ref "X4") (pin "12.2") (pinfunction "2_12.2") (pintype "passive"))
    )
    (net (code "102") (name "unconnected-(X4E-2-Pad13.2)") (class "Default")
      (node (ref "X4") (pin "13.2") (pinfunction "2_13.2") (pintype "passive"))
    )
    (net (code "103") (name "unconnected-(X4F-2-Pad14.2)") (class "Default")
      (node (ref "X4") (pin "14.2") (pinfunction "2_14.2") (pintype "passive"))
    )
    (net (code "104") (name "unconnected-(X4G-2-Pad15.2)") (class "Default")
      (node (ref "X4") (pin "15.2") (pinfunction "2_15.2") (pintype "passive"))
    )
    (net (code "105") (name "unconnected-(X4H-2-Pad2.2)") (class "Default")
      (node (ref "X4") (pin "2.2") (pinfunction "2_2.2") (pintype "passive"))
    )
    (net (code "106") (name "unconnected-(X4I-2-Pad3.2)") (class "Default")
      (node (ref "X4") (pin "3.2") (pinfunction "2_3.2") (pintype "passive"))
    )
    (net (code "107") (name "unconnected-(X4J-2-Pad4.2)") (class "Default")
      (node (ref "X4") (pin "4.2") (pinfunction "2_4.2") (pintype "passive"))
    )
    (net (code "108") (name "unconnected-(X4K-2-Pad5.2)") (class "Default")
      (node (ref "X4") (pin "5.2") (pinfunction "2_5.2") (pintype "passive"))
    )
    (net (code "109") (name "unconnected-(X4L-2-Pad6.2)") (class "Default")
      (node (ref "X4") (pin "6.2") (pinfunction "2_6.2") (pintype "passive"))
    )
    (net (code "110") (name "unconnected-(X4M-2-Pad7.2)") (class "Default")
      (node (ref "X4") (pin "7.2") (pinfunction "2_7.2") (pintype "passive"))
    )
    (net (code "111") (name "unconnected-(X4N-2-Pad8.2)") (class "Default")
      (node (ref "X4") (pin "8.2") (pinfunction "2_8.2") (pintype "passive"))
    )
    (net (code "112") (name "unconnected-(X4O-2-Pad9.2)") (class "Default")
      (node (ref "X4") (pin "9.2") (pinfunction "2_9.2") (pintype "passive"))
    )
    (net (code "113") (name "unconnected-(X5A-2-Pad1.2)") (class "Default")
      (node (ref "X5") (pin "1.2") (pinfunction "2_1.2") (pintype "passive"))
    )
    (net (code "114") (name "unconnected-(X5B-2-Pad10.2)") (class "Default")
      (node (ref "X5") (pin "10.2") (pinfunction "2_10.2") (pintype "passive"))
    )
    (net (code "115") (name "unconnected-(X5C-2-Pad11.2)") (class "Default")
      (node (ref "X5") (pin "11.2") (pinfunction "2_11.2") (pintype "passive"))
    )
    (net (code "116") (name "unconnected-(X5D-2-Pad12.2)") (class "Default")
      (node (ref "X5") (pin "12.2") (pinfunction "2_12.2") (pintype "passive"))
    )
    (net (code "117") (name "unconnected-(X5E-2-Pad13.2)") (class "Default")
      (node (ref "X5") (pin "13.2") (pinfunction "2_13.2") (pintype "passive"))
    )
    (net (code "118") (name "unconnected-(X5F-2-Pad14.2)") (class "Default")
      (node (ref "X5") (pin "14.2") (pinfunction "2_14.2") (pintype "passive"))
    )
    (net (code "119") (name "unconnected-(X5G-2-Pad15.2)") (class "Default")
      (node (ref "X5") (pin "15.2") (pinfunction "2_15.2") (pintype "passive"))
    )
    (net (code "120") (name "unconnected-(X5H-2-Pad2.2)") (class "Default")
      (node (ref "X5") (pin "2.2") (pinfunction "2_2.2") (pintype "passive"))
    )
    (net (code "121") (name "unconnected-(X5I-2-Pad3.2)") (class "Default")
      (node (ref "X5") (pin "3.2") (pinfunction "2_3.2") (pintype "passive"))
    )
    (net (code "122") (name "unconnected-(X5J-2-Pad4.2)") (class "Default")
      (node (ref "X5") (pin "4.2") (pinfunction "2_4.2") (pintype "passive"))
    )
    (net (code "123") (name "unconnected-(X5K-2-Pad5.2)") (class "Default")
      (node (ref "X5") (pin "5.2") (pinfunction "2_5.2") (pintype "passive"))
    )
    (net (code "124") (name "unconnected-(X5L-2-Pad6.2)") (class "Default")
      (node (ref "X5") (pin "6.2") (pinfunction "2_6.2") (pintype "passive"))
    )
    (net (code "125") (name "unconnected-(X5M-2-Pad7.2)") (class "Default")
      (node (ref "X5") (pin "7.2") (pinfunction "2_7.2") (pintype "passive"))
    )
    (net (code "126") (name "unconnected-(X5N-2-Pad8.2)") (class "Default")
      (node (ref "X5") (pin "8.2") (pinfunction "2_8.2") (pintype "passive"))
    )
    (net (code "127") (name "unconnected-(X5O-2-Pad9.2)") (class "Default")
      (node (ref "X5") (pin "9.2") (pinfunction "2_9.2") (pintype "passive"))
    )
  )
)
